# SNC8600.net
KiCad netlist of a schematic drawn in Altium Designer
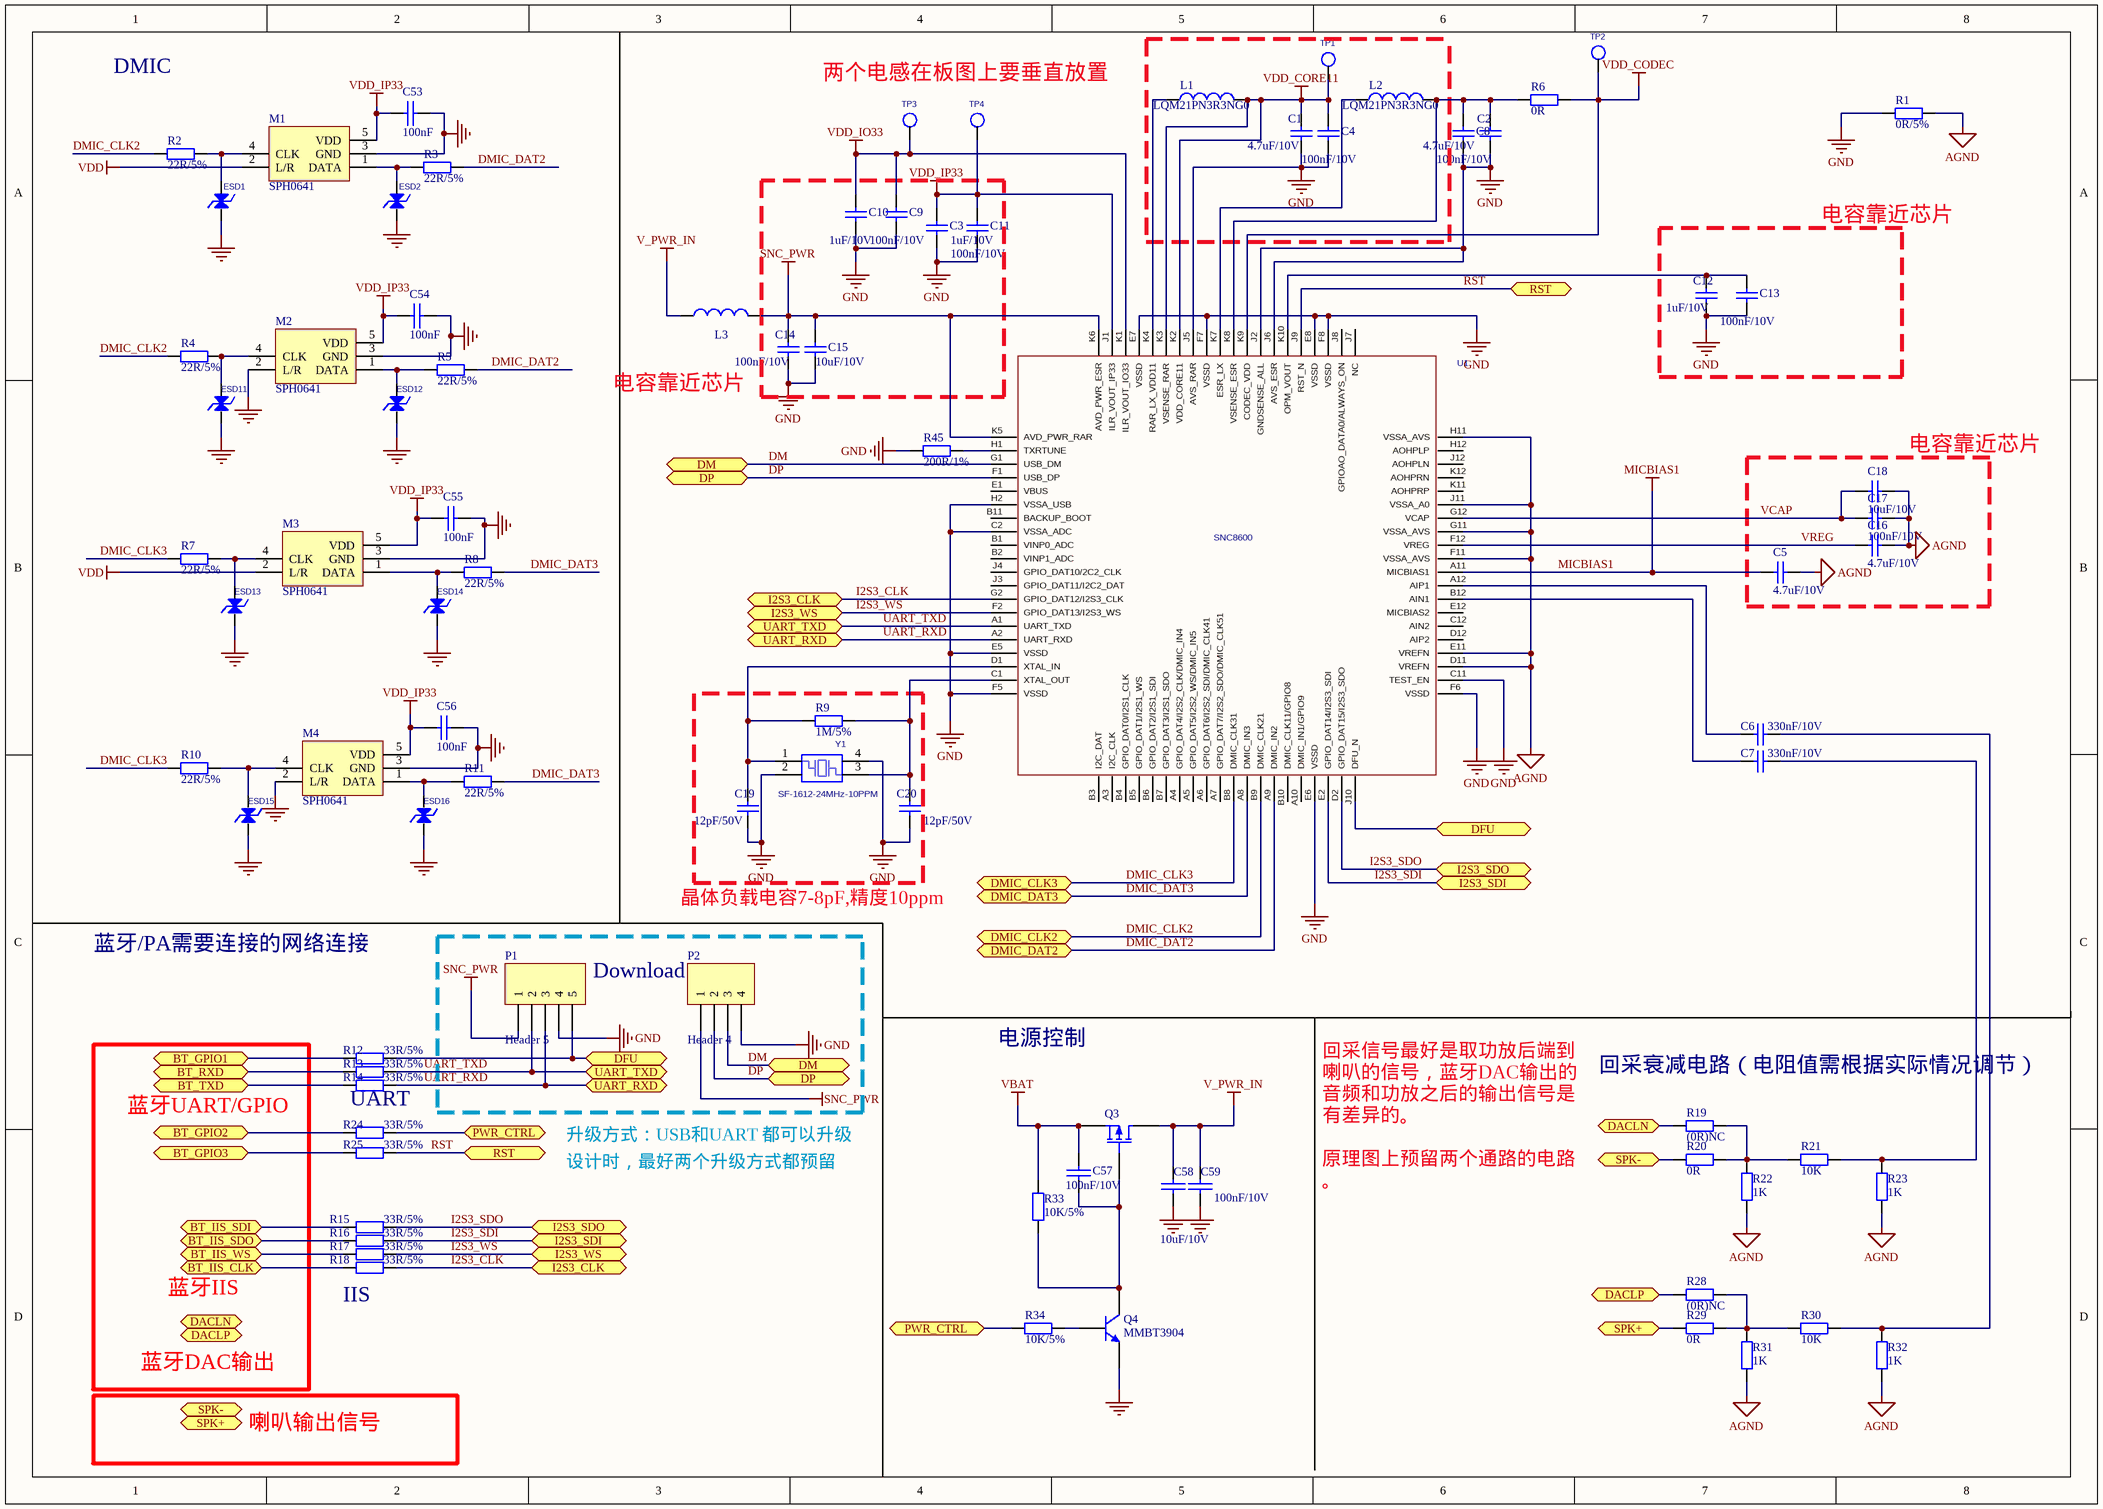
[diagram p0: SNC8600.SchDoc]

(export (version "E")
  (design (tool "Eeschema 10.0.6"))
  (components
    (comp (ref "C1")
      (value "4.7uF/10V")
      (footprint "C0603")
      (description "Capacitor (Semiconductor SIM Model)")
      (fields (field (name "PUBLISHER") "Altium Limited"))
      (libsource (lib "Miscellaneous Devices") (part "Cap Semi"))
    )
    (comp (ref "C2")
      (value "4.7uF/10V")
      (footprint "C0603")
      (description "Capacitor (Semiconductor SIM Model)")
      (fields (field (name "PUBLISHER") "Altium Limited"))
      (libsource (lib "Miscellaneous Devices") (part "Cap Semi"))
    )
    (comp (ref "C3")
      (value "1uF/10V")
      (footprint "C0603")
      (description "Capacitor (Semiconductor SIM Model)")
      (fields (field (name "PUBLISHER") "Altium Limited"))
      (libsource (lib "Miscellaneous Devices") (part "Cap Semi"))
    )
    (comp (ref "C4")
      (value "100nF/10V")
      (footprint "C0603")
      (description "Capacitor (Semiconductor SIM Model)")
      (fields (field (name "PUBLISHER") "Altium Limited"))
      (libsource (lib "Miscellaneous Devices") (part "Cap Semi"))
    )
    (comp (ref "C5")
      (value "4.7uF/10V")
      (footprint "C0603")
      (description "Capacitor (Semiconductor SIM Model)")
      (fields (field (name "PUBLISHER") "Altium Limited"))
      (libsource (lib "Miscellaneous Devices") (part "Cap Semi"))
    )
    (comp (ref "C6")
      (value "330nF/10V")
      (footprint "C0603")
      (description "Capacitor (Semiconductor SIM Model)")
      (fields (field (name "PUBLISHER") "Altium Limited"))
      (libsource (lib "Miscellaneous Devices") (part "Cap Semi"))
    )
    (comp (ref "C7")
      (value "330nF/10V")
      (footprint "C0603")
      (description "Capacitor (Semiconductor SIM Model)")
      (fields (field (name "PUBLISHER") "Altium Limited"))
      (libsource (lib "Miscellaneous Devices") (part "Cap Semi"))
    )
    (comp (ref "C8")
      (value "100nF/10V")
      (footprint "C0603")
      (description "Capacitor (Semiconductor SIM Model)")
      (fields (field (name "PUBLISHER") "Altium Limited"))
      (libsource (lib "Miscellaneous Devices") (part "Cap Semi"))
    )
    (comp (ref "C9")
      (value "100nF/10V")
      (footprint "C0603")
      (description "Capacitor (Semiconductor SIM Model)")
      (fields (field (name "PUBLISHER") "Altium Limited"))
      (libsource (lib "Miscellaneous Devices") (part "Cap Semi"))
    )
    (comp (ref "C10")
      (value "1uF/10V")
      (footprint "C0603")
      (description "Capacitor (Semiconductor SIM Model)")
      (fields (field (name "PUBLISHER") "Altium Limited"))
      (libsource (lib "Miscellaneous Devices") (part "Cap Semi"))
    )
    (comp (ref "C11")
      (value "100nF/10V")
      (footprint "C0603")
      (description "Capacitor (Semiconductor SIM Model)")
      (fields (field (name "PUBLISHER") "Altium Limited"))
      (libsource (lib "Miscellaneous Devices") (part "Cap Semi"))
    )
    (comp (ref "C12")
      (value "1uF/10V")
      (footprint "C0603")
      (description "Capacitor (Semiconductor SIM Model)")
      (fields (field (name "PUBLISHER") "Altium Limited"))
      (libsource (lib "Miscellaneous Devices") (part "Cap Semi"))
    )
    (comp (ref "C13")
      (value "100nF/10V")
      (footprint "C0603")
      (description "Capacitor (Semiconductor SIM Model)")
      (fields (field (name "PUBLISHER") "Altium Limited"))
      (libsource (lib "Miscellaneous Devices") (part "Cap Semi"))
    )
    (comp (ref "C14")
      (value "100nF/10V")
      (footprint "C0603")
      (description "Capacitor (Semiconductor SIM Model)")
      (fields (field (name "PUBLISHER") "Altium Limited"))
      (libsource (lib "Miscellaneous Devices") (part "Cap Semi"))
    )
    (comp (ref "C15")
      (value "10uF/10V")
      (footprint "C0603")
      (description "Capacitor (Semiconductor SIM Model)")
      (fields (field (name "PUBLISHER") "Altium Limited"))
      (libsource (lib "Miscellaneous Devices") (part "Cap Semi"))
    )
    (comp (ref "C16")
      (value "4.7uF/10V")
      (footprint "C0603")
      (description "Capacitor (Semiconductor SIM Model)")
      (fields (field (name "PUBLISHER") "Altium Limited"))
      (libsource (lib "Miscellaneous Devices") (part "Cap Semi"))
    )
    (comp (ref "C17")
      (value "100nF/10V")
      (footprint "C0603")
      (description "Capacitor (Semiconductor SIM Model)")
      (fields (field (name "PUBLISHER") "Altium Limited"))
      (libsource (lib "Miscellaneous Devices") (part "Cap Semi"))
    )
    (comp (ref "C18")
      (value "10uF/10V")
      (footprint "C0603")
      (description "Capacitor (Semiconductor SIM Model)")
      (fields (field (name "PUBLISHER") "Altium Limited"))
      (libsource (lib "Miscellaneous Devices") (part "Cap Semi"))
    )
    (comp (ref "C19")
      (value "12pF/50V")
      (footprint "C0603")
      (description "Capacitor (Semiconductor SIM Model)")
      (fields (field (name "PUBLISHER") "Altium Limited"))
      (libsource (lib "Miscellaneous Devices") (part "Cap Semi"))
    )
    (comp (ref "C20")
      (value "12pF/50V")
      (footprint "C0603")
      (description "Capacitor (Semiconductor SIM Model)")
      (fields (field (name "PUBLISHER") "Altium Limited"))
      (libsource (lib "Miscellaneous Devices") (part "Cap Semi"))
    )
    (comp (ref "C53")
      (value "100nF")
      (footprint "0201")
      (description "Capacitor")
      (libsource (lib "MIC1") (part "CAP-0201"))
    )
    (comp (ref "C54")
      (value "100nF")
      (footprint "0201")
      (description "Capacitor")
      (libsource (lib "MIC1") (part "CAP-0201"))
    )
    (comp (ref "C55")
      (value "100nF")
      (footprint "0201")
      (description "Capacitor")
      (libsource (lib "MIC1") (part "CAP-0201"))
    )
    (comp (ref "C56")
      (value "100nF")
      (footprint "0201")
      (description "Capacitor")
      (libsource (lib "MIC1") (part "CAP-0201"))
    )
    (comp (ref "C57")
      (value "100nF/10V")
      (footprint "0201")
      (description "Capacitor")
      (libsource (lib "*") (part "CAP"))
    )
    (comp (ref "C58")
      (value "10uF/10V")
      (footprint "C0402")
      (description "Capacitor")
      (libsource (lib "电容") (part "普通电容"))
    )
    (comp (ref "C59")
      (value "100nF/10V")
      (footprint "0201")
      (description "Capacitor")
      (libsource (lib "电容") (part "普通电容"))
    )
    (comp (ref "ESD1")
      (value "~")
      (footprint "0402 DFN")
      (libsource (lib "EVB-SCH-LCD-202003152") (part "ESD"))
    )
    (comp (ref "ESD2")
      (value "~")
      (footprint "0402 DFN")
      (libsource (lib "EVB-SCH-LCD-202003152") (part "ESD"))
    )
    (comp (ref "ESD11")
      (value "~")
      (footprint "0402 DFN")
      (libsource (lib "EVB-SCH-LCD-202003152") (part "ESD"))
    )
    (comp (ref "ESD12")
      (value "~")
      (footprint "0402 DFN")
      (libsource (lib "EVB-SCH-LCD-202003152") (part "ESD"))
    )
    (comp (ref "ESD13")
      (value "~")
      (footprint "0402 DFN")
      (libsource (lib "EVB-SCH-LCD-202003152") (part "ESD"))
    )
    (comp (ref "ESD14")
      (value "~")
      (footprint "0402 DFN")
      (libsource (lib "EVB-SCH-LCD-202003152") (part "ESD"))
    )
    (comp (ref "ESD15")
      (value "~")
      (footprint "0402 DFN")
      (libsource (lib "EVB-SCH-LCD-202003152") (part "ESD"))
    )
    (comp (ref "ESD16")
      (value "~")
      (footprint "0402 DFN")
      (libsource (lib "EVB-SCH-LCD-202003152") (part "ESD"))
    )
    (comp (ref "L1")
      (value "LQM21PN3R3NG0")
      (footprint "L0805")
      (description "Inductor")
      (fields (field (name "PUBLISHER") "Altium Limited"))
      (libsource (lib "Miscellaneous Devices") (part "Inductor"))
    )
    (comp (ref "L2")
      (value "LQM21PN3R3NG0")
      (footprint "L0805")
      (description "Inductor")
      (fields (field (name "PUBLISHER") "Altium Limited"))
      (libsource (lib "Miscellaneous Devices") (part "Inductor"))
    )
    (comp (ref "L3")
      (value "~")
      (footprint "R0402")
      (description "Inductor")
      (fields (field (name "PUBLISHER") "Altium Limited"))
      (libsource (lib "Miscellaneous Devices") (part "Inductor"))
    )
    (comp (ref "M1")
      (value "SPH0641")
      (footprint "SPH_3526")
      (description "MEMS MICPHONE")
      (fields (field (name "PUBLISHER") "Altium Limited"))
      (libsource (lib "MIC1") (part "SPH0641"))
    )
    (comp (ref "M2")
      (value "SPH0641")
      (footprint "SPH_3526")
      (description "MEMS MICPHONE")
      (fields (field (name "PUBLISHER") "Altium Limited"))
      (libsource (lib "MIC1") (part "SPH0641"))
    )
    (comp (ref "M3")
      (value "SPH0641")
      (footprint "SPH_3526")
      (description "MEMS MICPHONE")
      (fields (field (name "PUBLISHER") "Altium Limited"))
      (libsource (lib "MIC1") (part "SPH0641"))
    )
    (comp (ref "M4")
      (value "SPH0641")
      (footprint "SPH_3526")
      (description "MEMS MICPHONE")
      (fields (field (name "PUBLISHER") "Altium Limited"))
      (libsource (lib "MIC1") (part "SPH0641"))
    )
    (comp (ref "P1")
      (value "Header 5")
      (footprint "HDR1X5")
      (description "Header, 5-Pin")
      (fields (field (name "PUBLISHER") "Altium Limited"))
      (libsource (lib "Miscellaneous Connectors") (part "Header 5"))
    )
    (comp (ref "P2")
      (value "Header 4")
      (footprint "HDR1X4")
      (description "Header, 4-Pin")
      (fields (field (name "PUBLISHER") "Altium Limited"))
      (libsource (lib "Miscellaneous Connectors") (part "Header 4"))
    )
    (comp (ref "Q3")
      (value "~")
      (footprint "SOT23_3407")
      (description "P-Channel MOSFET")
      (fields (field (name "PUBLISHER") "Altium Limited"))
      (libsource (lib "Miscellaneous Devices") (part "MOSFET-P"))
    )
    (comp (ref "Q4")
      (value "MMBT3904")
      (footprint "SOT23")
      (description "NPN General Purpose Amplifier")
      (fields (field (name "PUBLISHER") "Altium Limited"))
      (libsource (lib "Miscellaneous Devices") (part "2N3904"))
    )
    (comp (ref "R1")
      (value "0R/5%")
      (footprint "R0603")
      (description "Resistor")
      (fields (field (name "PUBLISHER") "Altium Limited"))
      (libsource (lib "Miscellaneous Devices") (part "Res2"))
    )
    (comp (ref "R2")
      (value "22R/5%")
      (footprint "0201")
      (description "Resistor")
      (fields (field (name "PUBLISHER") "Altium Limited"))
      (libsource (lib "") (part "Res2_1"))
    )
    (comp (ref "R3")
      (value "22R/5%")
      (footprint "0201")
      (description "Resistor")
      (fields (field (name "PUBLISHER") "Altium Limited"))
      (libsource (lib "") (part "Res2_1"))
    )
    (comp (ref "R4")
      (value "22R/5%")
      (footprint "0201")
      (description "Resistor")
      (fields (field (name "PUBLISHER") "Altium Limited"))
      (libsource (lib "") (part "Res2_1"))
    )
    (comp (ref "R5")
      (value "22R/5%")
      (footprint "0201")
      (description "Resistor")
      (fields (field (name "PUBLISHER") "Altium Limited"))
      (libsource (lib "") (part "Res2_1"))
    )
    (comp (ref "R6")
      (value "0R")
      (footprint "R0603")
      (description "Resistor")
      (fields (field (name "PUBLISHER") "Altium Limited"))
      (libsource (lib "Miscellaneous Devices") (part "Res2"))
    )
    (comp (ref "R7")
      (value "22R/5%")
      (footprint "0201")
      (description "Resistor")
      (fields (field (name "PUBLISHER") "Altium Limited"))
      (libsource (lib "") (part "Res2_1"))
    )
    (comp (ref "R8")
      (value "22R/5%")
      (footprint "0201")
      (description "Resistor")
      (fields (field (name "PUBLISHER") "Altium Limited"))
      (libsource (lib "") (part "Res2_1"))
    )
    (comp (ref "R9")
      (value "1M/5%")
      (footprint "R0603")
      (description "Resistor")
      (fields (field (name "PUBLISHER") "Altium Limited"))
      (libsource (lib "Miscellaneous Devices") (part "Res2"))
    )
    (comp (ref "R10")
      (value "22R/5%")
      (footprint "0201")
      (description "Resistor")
      (fields (field (name "PUBLISHER") "Altium Limited"))
      (libsource (lib "") (part "Res2_1"))
    )
    (comp (ref "R11")
      (value "22R/5%")
      (footprint "0201")
      (description "Resistor")
      (fields (field (name "PUBLISHER") "Altium Limited"))
      (libsource (lib "") (part "Res2_1"))
    )
    (comp (ref "R12")
      (value "33R/5%")
      (footprint "R0603")
      (description "Resistor")
      (fields (field (name "PUBLISHER") "Altium Limited"))
      (libsource (lib "") (part "Res2_1"))
    )
    (comp (ref "R13")
      (value "33R/5%")
      (footprint "R0603")
      (description "Resistor")
      (fields (field (name "PUBLISHER") "Altium Limited"))
      (libsource (lib "") (part "Res2_1"))
    )
    (comp (ref "R14")
      (value "33R/5%")
      (footprint "R0603")
      (description "Resistor")
      (fields (field (name "PUBLISHER") "Altium Limited"))
      (libsource (lib "") (part "Res2_1"))
    )
    (comp (ref "R15")
      (value "33R/5%")
      (footprint "R0603")
      (description "Resistor")
      (fields (field (name "PUBLISHER") "Altium Limited"))
      (libsource (lib "") (part "Res2_1"))
    )
    (comp (ref "R16")
      (value "33R/5%")
      (footprint "R0603")
      (description "Resistor")
      (fields (field (name "PUBLISHER") "Altium Limited"))
      (libsource (lib "") (part "Res2_1"))
    )
    (comp (ref "R17")
      (value "33R/5%")
      (footprint "R0603")
      (description "Resistor")
      (fields (field (name "PUBLISHER") "Altium Limited"))
      (libsource (lib "") (part "Res2_1"))
    )
    (comp (ref "R18")
      (value "33R/5%")
      (footprint "R0603")
      (description "Resistor")
      (fields (field (name "PUBLISHER") "Altium Limited"))
      (libsource (lib "") (part "Res2_1"))
    )
    (comp (ref "R19")
      (value "(0R)NC")
      (footprint "R0603")
      (description "Resistor")
      (fields (field (name "PUBLISHER") "Altium Limited"))
      (libsource (lib "Miscellaneous Devices") (part "Res2"))
    )
    (comp (ref "R20")
      (value "0R")
      (footprint "R0603")
      (description "Resistor")
      (fields (field (name "PUBLISHER") "Altium Limited"))
      (libsource (lib "Miscellaneous Devices") (part "Res2"))
    )
    (comp (ref "R21")
      (value "10K")
      (footprint "R0603")
      (description "Resistor")
      (fields (field (name "PUBLISHER") "Altium Limited"))
      (libsource (lib "Miscellaneous Devices") (part "Res2"))
    )
    (comp (ref "R22")
      (value "1K")
      (footprint "R0603")
      (description "Resistor")
      (fields (field (name "PUBLISHER") "Altium Limited"))
      (libsource (lib "") (part "Res2_2"))
    )
    (comp (ref "R23")
      (value "1K")
      (footprint "R0603")
      (description "Resistor")
      (fields (field (name "PUBLISHER") "Altium Limited"))
      (libsource (lib "") (part "Res2_2"))
    )
    (comp (ref "R24")
      (value "33R/5%")
      (footprint "R0603")
      (description "Resistor")
      (fields (field (name "PUBLISHER") "Altium Limited"))
      (libsource (lib "") (part "Res2_1"))
    )
    (comp (ref "R25")
      (value "33R/5%")
      (footprint "R0603")
      (description "Resistor")
      (fields (field (name "PUBLISHER") "Altium Limited"))
      (libsource (lib "") (part "Res2_1"))
    )
    (comp (ref "R28")
      (value "(0R)NC")
      (footprint "R0603")
      (description "Resistor")
      (fields (field (name "PUBLISHER") "Altium Limited"))
      (libsource (lib "Miscellaneous Devices") (part "Res2"))
    )
    (comp (ref "R29")
      (value "0R")
      (footprint "R0603")
      (description "Resistor")
      (fields (field (name "PUBLISHER") "Altium Limited"))
      (libsource (lib "Miscellaneous Devices") (part "Res2"))
    )
    (comp (ref "R30")
      (value "10K")
      (footprint "R0603")
      (description "Resistor")
      (fields (field (name "PUBLISHER") "Altium Limited"))
      (libsource (lib "Miscellaneous Devices") (part "Res2"))
    )
    (comp (ref "R31")
      (value "1K")
      (footprint "R0603")
      (description "Resistor")
      (fields (field (name "PUBLISHER") "Altium Limited"))
      (libsource (lib "") (part "Res2_2"))
    )
    (comp (ref "R32")
      (value "1K")
      (footprint "R0603")
      (description "Resistor")
      (fields (field (name "PUBLISHER") "Altium Limited"))
      (libsource (lib "") (part "Res2_2"))
    )
    (comp (ref "R33")
      (value "10K/5%")
      (footprint "0201")
      (description "Resistor")
      (fields (field (name "PUBLISHER") "Altium Limited"))
      (libsource (lib "") (part "Res2_2"))
    )
    (comp (ref "R34")
      (value "10K/5%")
      (footprint "0201")
      (description "Resistor")
      (fields (field (name "PUBLISHER") "Altium Limited"))
      (libsource (lib "") (part "Res2_1"))
    )
    (comp (ref "R45")
      (value "200R/1%")
      (footprint "R0603")
      (description "Resistor")
      (fields (field (name "PUBLISHER") "Altium Limited"))
      (libsource (lib "") (part "Res2_1"))
    )
    (comp (ref "TP1")
      (value "TP1")
      (footprint "TP1-1MM")
      (libsource (lib "EVB-SCH-LCD-202003152") (part "TP1"))
    )
    (comp (ref "TP2")
      (value "TP1")
      (footprint "TP1-1MM")
      (libsource (lib "EVB-SCH-LCD-202003152") (part "TP1"))
    )
    (comp (ref "TP3")
      (value "TP1")
      (footprint "TP1-1MM")
      (libsource (lib "EVB-SCH-LCD-202003152") (part "TP1"))
    )
    (comp (ref "TP4")
      (value "TP1")
      (footprint "TP1-1MM")
      (libsource (lib "EVB-SCH-LCD-202003152") (part "TP1"))
    )
    (comp (ref "U1")
      (value "SNC8600")
      (footprint "BGA0405-2")
      (libsource (lib "EVB-SCH-LCD-202003152") (part "BGA_BCHIP-ES2"))
    )
    (comp (ref "Y1")
      (value "SF-1612-24MHz-10PPM")
      (footprint "SF1612")
      (fields (field (name "Comment") "SF1612"))
      (libsource (lib "EVB-SCH-LCD-202003152") (part "SF1612"))
    )
  )
  (nets
    (net (code "1") (name "/BT_GPIO1") (class "Default")
      (node (ref "R12") (pin "1") (pinfunction "1_1") (pintype "passive"))
    )
    (net (code "2") (name "/BT_GPIO2") (class "Default")
      (node (ref "R24") (pin "1") (pinfunction "1_1") (pintype "passive"))
    )
    (net (code "3") (name "/BT_GPIO3") (class "Default")
      (node (ref "R25") (pin "1") (pinfunction "1_1") (pintype "passive"))
    )
    (net (code "4") (name "/BT_IIS_CLK") (class "Default")
      (node (ref "R18") (pin "1") (pinfunction "1_1") (pintype "passive"))
    )
    (net (code "5") (name "/BT_IIS_SDI") (class "Default")
      (node (ref "R15") (pin "1") (pinfunction "1_1") (pintype "passive"))
    )
    (net (code "6") (name "/BT_IIS_SDO") (class "Default")
      (node (ref "R16") (pin "1") (pinfunction "1_1") (pintype "passive"))
    )
    (net (code "7") (name "/BT_IIS_WS") (class "Default")
      (node (ref "R17") (pin "1") (pinfunction "1_1") (pintype "passive"))
    )
    (net (code "8") (name "/BT_RXD") (class "Default")
      (node (ref "R13") (pin "1") (pinfunction "1_1") (pintype "passive"))
    )
    (net (code "9") (name "/BT_TXD") (class "Default")
      (node (ref "R14") (pin "1") (pinfunction "1_1") (pintype "passive"))
    )
    (net (code "10") (name "/DACLN") (class "Default")
      (node (ref "R19") (pin "2") (pinfunction "2_2") (pintype "passive"))
    )
    (net (code "11") (name "/DACLP") (class "Default")
      (node (ref "R28") (pin "2") (pinfunction "2_2") (pintype "passive"))
    )
    (net (code "12") (name "/DFU") (class "Default")
      (node (ref "P1") (pin "5") (pinfunction "5_5") (pintype "passive"))
      (node (ref "R12") (pin "2") (pinfunction "2_2") (pintype "passive"))
      (node (ref "U1") (pin "J10") (pinfunction "DFU_N_J10") (pintype "passive"))
    )
    (net (code "13") (name "/DM") (class "Default")
      (node (ref "P2") (pin "3") (pinfunction "3_3") (pintype "passive"))
      (node (ref "U1") (pin "G1") (pinfunction "USB_DM_G1") (pintype "passive"))
    )
    (net (code "14") (name "/DMIC_CLK2") (class "Default")
      (node (ref "R2") (pin "1") (pinfunction "1_1") (pintype "passive"))
      (node (ref "R4") (pin "1") (pinfunction "1_1") (pintype "passive"))
      (node (ref "U1") (pin "B9") (pinfunction "DMIC_CLK21_B9") (pintype "passive"))
    )
    (net (code "15") (name "/DMIC_CLK3") (class "Default")
      (node (ref "R10") (pin "1") (pinfunction "1_1") (pintype "passive"))
      (node (ref "R7") (pin "1") (pinfunction "1_1") (pintype "passive"))
      (node (ref "U1") (pin "B8") (pinfunction "DMIC_CLK31_B8") (pintype "passive"))
    )
    (net (code "16") (name "/DMIC_DAT2") (class "Default")
      (node (ref "R3") (pin "2") (pinfunction "2_2") (pintype "passive"))
      (node (ref "R5") (pin "2") (pinfunction "2_2") (pintype "passive"))
      (node (ref "U1") (pin "A9") (pinfunction "DMIC_IN2_A9") (pintype "passive"))
    )
    (net (code "17") (name "/DMIC_DAT3") (class "Default")
      (node (ref "R11") (pin "2") (pinfunction "2_2") (pintype "passive"))
      (node (ref "R8") (pin "2") (pinfunction "2_2") (pintype "passive"))
      (node (ref "U1") (pin "A8") (pinfunction "DMIC_IN3_A8") (pintype "passive"))
    )
    (net (code "18") (name "/DP") (class "Default")
      (node (ref "P2") (pin "2") (pinfunction "2_2") (pintype "passive"))
      (node (ref "U1") (pin "F1") (pinfunction "USB_DP_F1") (pintype "passive"))
    )
    (net (code "19") (name "/I2S3_CLK") (class "Default")
      (node (ref "R18") (pin "2") (pinfunction "2_2") (pintype "passive"))
      (node (ref "U1") (pin "G2") (pinfunction "GPIO_DAT12/I2S3_CLK_G2") (pintype "passive"))
    )
    (net (code "20") (name "/I2S3_SDI") (class "Default")
      (node (ref "R16") (pin "2") (pinfunction "2_2") (pintype "passive"))
      (node (ref "U1") (pin "E2") (pinfunction "GPIO_DAT14/I2S3_SDI_E2") (pintype "passive"))
    )
    (net (code "21") (name "/I2S3_SDO") (class "Default")
      (node (ref "R15") (pin "2") (pinfunction "2_2") (pintype "passive"))
      (node (ref "U1") (pin "D2") (pinfunction "GPIO_DAT15/I2S3_SDO_D2") (pintype "passive"))
    )
    (net (code "22") (name "/I2S3_WS") (class "Default")
      (node (ref "R17") (pin "2") (pinfunction "2_2") (pintype "passive"))
      (node (ref "U1") (pin "F2") (pinfunction "GPIO_DAT13/I2S3_WS_F2") (pintype "passive"))
    )
    (net (code "23") (name "/PWR_CTRL") (class "Default")
      (node (ref "R24") (pin "2") (pinfunction "2_2") (pintype "passive"))
      (node (ref "R34") (pin "1") (pinfunction "1_1") (pintype "passive"))
    )
    (net (code "24") (name "/RST") (class "Default")
      (node (ref "R25") (pin "2") (pinfunction "2_2") (pintype "passive"))
      (node (ref "U1") (pin "J9") (pinfunction "RST_N_J9") (pintype "passive"))
    )
    (net (code "25") (name "/SPK+") (class "Default")
      (node (ref "R29") (pin "2") (pinfunction "2_2") (pintype "passive"))
    )
    (net (code "26") (name "/SPK-") (class "Default")
      (node (ref "R20") (pin "2") (pinfunction "2_2") (pintype "passive"))
    )
    (net (code "27") (name "/UART_RXD") (class "Default")
      (node (ref "P1") (pin "3") (pinfunction "3_3") (pintype "passive"))
      (node (ref "R14") (pin "2") (pinfunction "2_2") (pintype "passive"))
      (node (ref "U1") (pin "A2") (pinfunction "UART_RXD_A2") (pintype "passive"))
    )
    (net (code "28") (name "/UART_TXD") (class "Default")
      (node (ref "P1") (pin "2") (pinfunction "2_2") (pintype "passive"))
      (node (ref "R13") (pin "2") (pinfunction "2_2") (pintype "passive"))
      (node (ref "U1") (pin "A1") (pinfunction "UART_TXD_A1") (pintype "passive"))
    )
    (net (code "29") (name "/VCAP") (class "Default")
      (node (ref "C17") (pin "2") (pinfunction "2_2") (pintype "passive"))
      (node (ref "C18") (pin "2") (pinfunction "2_2") (pintype "passive"))
      (node (ref "U1") (pin "G12") (pinfunction "VCAP_G12") (pintype "passive"))
    )
    (net (code "30") (name "/VREG") (class "Default")
      (node (ref "C16") (pin "2") (pinfunction "2_2") (pintype "passive"))
      (node (ref "U1") (pin "F12") (pinfunction "VREG_F12") (pintype "passive"))
    )
    (net (code "31") (name "AGND") (class "Default")
      (node (ref "C16") (pin "1") (pinfunction "1_1") (pintype "passive"))
      (node (ref "C17") (pin "1") (pinfunction "1_1") (pintype "passive"))
      (node (ref "C18") (pin "1") (pinfunction "1_1") (pintype "passive"))
      (node (ref "C5") (pin "1") (pinfunction "1_1") (pintype "passive"))
      (node (ref "R1") (pin "1") (pinfunction "1_1") (pintype "passive"))
      (node (ref "R22") (pin "2") (pinfunction "2_2") (pintype "passive"))
      (node (ref "R23") (pin "2") (pinfunction "2_2") (pintype "passive"))
      (node (ref "R31") (pin "2") (pinfunction "2_2") (pintype "passive"))
      (node (ref "R32") (pin "2") (pinfunction "2_2") (pintype "passive"))
      (node (ref "U1") (pin "D11") (pinfunction "VREFN_D11") (pintype "passive"))
      (node (ref "U1") (pin "E11") (pinfunction "VREFN_E11") (pintype "passive"))
      (node (ref "U1") (pin "F11") (pinfunction "VSSA_AVS_F11") (pintype "passive"))
      (node (ref "U1") (pin "G11") (pinfunction "VSSA_AVS_G11") (pintype "passive"))
      (node (ref "U1") (pin "H11") (pinfunction "VSSA_AVS_H11") (pintype "passive"))
      (node (ref "U1") (pin "J11") (pinfunction "VSSA_A0_J11") (pintype "passive"))
    )
    (net (code "32") (name "GND") (class "Default")
      (node (ref "C1") (pin "1") (pinfunction "1_1") (pintype "passive"))
      (node (ref "C10") (pin "1") (pinfunction "1_1") (pintype "passive"))
      (node (ref "C11") (pin "1") (pinfunction "1_1") (pintype "passive"))
      (node (ref "C12") (pin "1") (pinfunction "1_1") (pintype "passive"))
      (node (ref "C13") (pin "1") (pinfunction "1_1") (pintype "passive"))
      (node (ref "C14") (pin "1") (pinfunction "1_1") (pintype "passive"))
      (node (ref "C15") (pin "1") (pinfunction "1_1") (pintype "passive"))
      (node (ref "C19") (pin "1") (pinfunction "1_1") (pintype "passive"))
      (node (ref "C2") (pin "1") (pinfunction "1_1") (pintype "passive"))
      (node (ref "C20") (pin "1") (pinfunction "1_1") (pintype "passive"))
      (node (ref "C3") (pin "1") (pinfunction "1_1") (pintype "passive"))
      (node (ref "C4") (pin "1") (pinfunction "1_1") (pintype "passive"))
      (node (ref "C53") (pin "1") (pinfunction "1_1") (pintype "passive"))
      (node (ref "C54") (pin "1") (pinfunction "1_1") (pintype "passive"))
      (node (ref "C55") (pin "1") (pinfunction "1_1") (pintype "passive"))
      (node (ref "C56") (pin "1") (pinfunction "1_1") (pintype "passive"))
      (node (ref "C58") (pin "1") (pinfunction "1_1") (pintype "passive"))
      (node (ref "C59") (pin "1") (pinfunction "1_1") (pintype "passive"))
      (node (ref "C8") (pin "1") (pinfunction "1_1") (pintype "passive"))
      (node (ref "C9") (pin "1") (pinfunction "1_1") (pintype "passive"))
      (node (ref "ESD1") (pin "2") (pinfunction "2_2") (pintype "passive"))
      (node (ref "ESD11") (pin "2") (pinfunction "2_2") (pintype "passive"))
      (node (ref "ESD12") (pin "2") (pinfunction "2_2") (pintype "passive"))
      (node (ref "ESD13") (pin "2") (pinfunction "2_2") (pintype "passive"))
      (node (ref "ESD14") (pin "2") (pinfunction "2_2") (pintype "passive"))
      (node (ref "ESD15") (pin "2") (pinfunction "2_2") (pintype "passive"))
      (node (ref "ESD16") (pin "2") (pinfunction "2_2") (pintype "passive"))
      (node (ref "ESD2") (pin "2") (pinfunction "2_2") (pintype "passive"))
      (node (ref "M1") (pin "3") (pinfunction "GND_3") (pintype "power_in"))
      (node (ref "M2") (pin "2") (pinfunction "L/R_2") (pintype "passive"))
      (node (ref "M2") (pin "3") (pinfunction "GND_3") (pintype "power_in"))
      (node (ref "M3") (pin "3") (pinfunction "GND_3") (pintype "power_in"))
      (node (ref "M4") (pin "2") (pinfunction "L/R_2") (pintype "passive"))
      (node (ref "M4") (pin "3") (pinfunction "GND_3") (pintype "power_in"))
      (node (ref "P1") (pin "4") (pinfunction "4_4") (pintype "passive"))
      (node (ref "P2") (pin "4") (pinfunction "4_4") (pintype "passive"))
      (node (ref "Q4") (pin "2") (pinfunction "E_2") (pintype "passive"))
      (node (ref "R1") (pin "2") (pinfunction "2_2") (pintype "passive"))
      (node (ref "R45") (pin "1") (pinfunction "1_1") (pintype "passive"))
      (node (ref "U1") (pin "C11") (pinfunction "TEST_EN_C11") (pintype "passive"))
      (node (ref "U1") (pin "C2") (pinfunction "VSSA_ADC_C2") (pintype "passive"))
      (node (ref "U1") (pin "E5") (pinfunction "VSSD_E5") (pintype "passive"))
      (node (ref "U1") (pin "E6") (pinfunction "VSSD_E6") (pintype "passive"))
      (node (ref "U1") (pin "E7") (pinfunction "VSSD_E7") (pintype "passive"))
      (node (ref "U1") (pin "E8") (pinfunction "VSSD_E8") (pintype "passive"))
      (node (ref "U1") (pin "F5") (pinfunction "VSSD_F5") (pintype "passive"))
      (node (ref "U1") (pin "F6") (pinfunction "VSSD_F6") (pintype "passive"))
      (node (ref "U1") (pin "F7") (pinfunction "VSSD_F7") (pintype "passive"))
      (node (ref "U1") (pin "F8") (pinfunction "VSSD_F8") (pintype "passive"))
      (node (ref "U1") (pin "H2") (pinfunction "VSSA_USB_H2") (pintype "passive"))
      (node (ref "U1") (pin "J2") (pinfunction "GNDSENSE_ALL_J2") (pintype "passive"))
      (node (ref "U1") (pin "J5") (pinfunction "AVS_RAR_J5") (pintype "passive"))
      (node (ref "U1") (pin "J6") (pinfunction "AVS_ESR_J6") (pintype "passive"))
      (node (ref "Y1") (pin "2") (pinfunction "2_2") (pintype "passive"))
      (node (ref "Y1") (pin "4") (pinfunction "4_4") (pintype "passive"))
    )
    (net (code "33") (name "MICBIAS1") (class "Default")
      (node (ref "C5") (pin "2") (pinfunction "2_2") (pintype "passive"))
      (node (ref "U1") (pin "A11") (pinfunction "MICBIAS1_A11") (pintype "passive"))
    )
    (net (code "34") (name "Net-(C6-Pad1)") (class "Default")
      (node (ref "C6") (pin "1") (pinfunction "1_1") (pintype "passive"))
      (node (ref "R30") (pin "1") (pinfunction "1_1") (pintype "passive"))
      (node (ref "R32") (pin "1") (pinfunction "1_1") (pintype "passive"))
    )
    (net (code "35") (name "Net-(C7-Pad1)") (class "Default")
      (node (ref "C7") (pin "1") (pinfunction "1_1") (pintype "passive"))
      (node (ref "R21") (pin "1") (pinfunction "1_1") (pintype "passive"))
      (node (ref "R23") (pin "1") (pinfunction "1_1") (pintype "passive"))
    )
    (net (code "36") (name "Net-(M1-CLK)") (class "Default")
      (node (ref "ESD1") (pin "1") (pinfunction "1_1") (pintype "passive"))
      (node (ref "M1") (pin "4") (pinfunction "CLK_4") (pintype "power_in"))
      (node (ref "R2") (pin "2") (pinfunction "2_2") (pintype "passive"))
    )
    (net (code "37") (name "Net-(M1-DATA)") (class "Default")
      (node (ref "ESD2") (pin "1") (pinfunction "1_1") (pintype "passive"))
      (node (ref "M1") (pin "1") (pinfunction "DATA_1") (pintype "passive"))
      (node (ref "R3") (pin "1") (pinfunction "1_1") (pintype "passive"))
    )
    (net (code "38") (name "Net-(M2-CLK)") (class "Default")
      (node (ref "ESD11") (pin "1") (pinfunction "1_1") (pintype "passive"))
      (node (ref "M2") (pin "4") (pinfunction "CLK_4") (pintype "power_in"))
      (node (ref "R4") (pin "2") (pinfunction "2_2") (pintype "passive"))
    )
    (net (code "39") (name "Net-(M2-DATA)") (class "Default")
      (node (ref "ESD12") (pin "1") (pinfunction "1_1") (pintype "passive"))
      (node (ref "M2") (pin "1") (pinfunction "DATA_1") (pintype "passive"))
      (node (ref "R5") (pin "1") (pinfunction "1_1") (pintype "passive"))
    )
    (net (code "40") (name "Net-(M3-CLK)") (class "Default")
      (node (ref "ESD13") (pin "1") (pinfunction "1_1") (pintype "passive"))
      (node (ref "M3") (pin "4") (pinfunction "CLK_4") (pintype "power_in"))
      (node (ref "R7") (pin "2") (pinfunction "2_2") (pintype "passive"))
    )
    (net (code "41") (name "Net-(M3-DATA)") (class "Default")
      (node (ref "ESD14") (pin "1") (pinfunction "1_1") (pintype "passive"))
      (node (ref "M3") (pin "1") (pinfunction "DATA_1") (pintype "passive"))
      (node (ref "R8") (pin "1") (pinfunction "1_1") (pintype "passive"))
    )
    (net (code "42") (name "Net-(M4-CLK)") (class "Default")
      (node (ref "ESD15") (pin "1") (pinfunction "1_1") (pintype "passive"))
      (node (ref "M4") (pin "4") (pinfunction "CLK_4") (pintype "power_in"))
      (node (ref "R10") (pin "2") (pinfunction "2_2") (pintype "passive"))
    )
    (net (code "43") (name "Net-(M4-DATA)") (class "Default")
      (node (ref "ESD16") (pin "1") (pinfunction "1_1") (pintype "passive"))
      (node (ref "M4") (pin "1") (pinfunction "DATA_1") (pintype "passive"))
      (node (ref "R11") (pin "1") (pinfunction "1_1") (pintype "passive"))
    )
    (net (code "44") (name "Net-(Q3-G)") (class "Default")
      (node (ref "C57") (pin "1") (pinfunction "1_1") (pintype "passive"))
      (node (ref "Q3") (pin "2") (pinfunction "G_2") (pintype "passive"))
      (node (ref "Q4") (pin "3") (pinfunction "C_3") (pintype "passive"))
      (node (ref "R33") (pin "2") (pinfunction "2_2") (pintype "passive"))
    )
    (net (code "45") (name "Net-(Q4-B)") (class "Default")
      (node (ref "Q4") (pin "1") (pinfunction "B_1") (pintype "passive"))
      (node (ref "R34") (pin "2") (pinfunction "2_2") (pintype "passive"))
    )
    (net (code "46") (name "Net-(R19-Pad1)") (class "Default")
      (node (ref "R19") (pin "1") (pinfunction "1_1") (pintype "passive"))
      (node (ref "R20") (pin "1") (pinfunction "1_1") (pintype "passive"))
      (node (ref "R21") (pin "2") (pinfunction "2_2") (pintype "passive"))
      (node (ref "R22") (pin "1") (pinfunction "1_1") (pintype "passive"))
    )
    (net (code "47") (name "Net-(R28-Pad1)") (class "Default")
      (node (ref "R28") (pin "1") (pinfunction "1_1") (pintype "passive"))
      (node (ref "R29") (pin "1") (pinfunction "1_1") (pintype "passive"))
      (node (ref "R30") (pin "2") (pinfunction "2_2") (pintype "passive"))
      (node (ref "R31") (pin "1") (pinfunction "1_1") (pintype "passive"))
    )
    (net (code "48") (name "Net-(U1-AIN1)") (class "Default")
      (node (ref "C7") (pin "2") (pinfunction "2_2") (pintype "passive"))
      (node (ref "U1") (pin "B12") (pinfunction "AIN1_B12") (pintype "passive"))
    )
    (net (code "49") (name "Net-(U1-AIP1)") (class "Default")
      (node (ref "C6") (pin "2") (pinfunction "2_2") (pintype "passive"))
      (node (ref "U1") (pin "A12") (pinfunction "AIP1_A12") (pintype "passive"))
    )
    (net (code "50") (name "Net-(U1-ESR_LX)") (class "Default")
      (node (ref "L2") (pin "1") (pinfunction "1_1") (pintype "passive"))
      (node (ref "U1") (pin "K7") (pinfunction "ESR_LX_K7") (pintype "passive"))
    )
    (net (code "51") (name "Net-(U1-OPM_VOUT)") (class "Default")
      (node (ref "C12") (pin "2") (pinfunction "2_2") (pintype "passive"))
      (node (ref "C13") (pin "2") (pinfunction "2_2") (pintype "passive"))
      (node (ref "U1") (pin "K10") (pinfunction "OPM_VOUT_K10") (pintype "passive"))
    )
    (net (code "52") (name "Net-(U1-RAR_LX_VDD11)") (class "Default")
      (node (ref "L1") (pin "1") (pinfunction "1_1") (pintype "passive"))
      (node (ref "U1") (pin "K4") (pinfunction "RAR_LX_VDD11_K4") (pintype "passive"))
    )
    (net (code "53") (name "Net-(U1-TXRTUNE)") (class "Default")
      (node (ref "R45") (pin "2") (pinfunction "2_2") (pintype "passive"))
      (node (ref "U1") (pin "H1") (pinfunction "TXRTUNE_H1") (pintype "passive"))
    )
    (net (code "54") (name "Net-(U1-VSENSE_ESR)") (class "Default")
      (node (ref "C2") (pin "2") (pinfunction "2_2") (pintype "passive"))
      (node (ref "C8") (pin "2") (pinfunction "2_2") (pintype "passive"))
      (node (ref "L2") (pin "2") (pinfunction "2_2") (pintype "passive"))
      (node (ref "R6") (pin "2") (pinfunction "2_2") (pintype "passive"))
      (node (ref "U1") (pin "K8") (pinfunction "VSENSE_ESR_K8") (pintype "passive"))
    )
    (net (code "55") (name "Net-(U1-XTAL_IN)") (class "Default")
      (node (ref "C19") (pin "2") (pinfunction "2_2") (pintype "passive"))
      (node (ref "R9") (pin "2") (pinfunction "2_2") (pintype "passive"))
      (node (ref "U1") (pin "D1") (pinfunction "XTAL_IN_D1") (pintype "passive"))
      (node (ref "Y1") (pin "1") (pinfunction "1_1") (pintype "passive"))
    )
    (net (code "56") (name "Net-(U1-XTAL_OUT)") (class "Default")
      (node (ref "C20") (pin "2") (pinfunction "2_2") (pintype "passive"))
      (node (ref "R9") (pin "1") (pinfunction "1_1") (pintype "passive"))
      (node (ref "U1") (pin "C1") (pinfunction "XTAL_OUT_C1") (pintype "passive"))
      (node (ref "Y1") (pin "3") (pinfunction "3_3") (pintype "passive"))
    )
    (net (code "57") (name "SNC_PWR") (class "Default")
      (node (ref "C14") (pin "2") (pinfunction "2_2") (pintype "passive"))
      (node (ref "C15") (pin "2") (pinfunction "2_2") (pintype "passive"))
      (node (ref "L3") (pin "2") (pinfunction "2_2") (pintype "passive"))
      (node (ref "P1") (pin "1") (pinfunction "1_1") (pintype "passive"))
      (node (ref "P2") (pin "1") (pinfunction "1_1") (pintype "passive"))
      (node (ref "U1") (pin "K5") (pinfunction "AVD_PWR_RAR_K5") (pintype "passive"))
      (node (ref "U1") (pin "K6") (pinfunction "AVD_PWR_ESR_K6") (pintype "passive"))
    )
    (net (code "58") (name "VBAT") (class "Default")
      (node (ref "C57") (pin "2") (pinfunction "2_2") (pintype "passive"))
      (node (ref "Q3") (pin "3") (pinfunction "S_3") (pintype "passive"))
      (node (ref "R33") (pin "1") (pinfunction "1_1") (pintype "passive"))
    )
    (net (code "59") (name "VDD") (class "Default")
      (node (ref "M1") (pin "2") (pinfunction "L/R_2") (pintype "passive"))
      (node (ref "M3") (pin "2") (pinfunction "L/R_2") (pintype "passive"))
    )
    (net (code "60") (name "VDD_CODEC") (class "Default")
      (node (ref "R6") (pin "1") (pinfunction "1_1") (pintype "passive"))
      (node (ref "TP2") (pin "1") (pinfunction "1_1") (pintype "passive"))
      (node (ref "U1") (pin "K9") (pinfunction "CODEC_VDD_K9") (pintype "passive"))
    )
    (net (code "61") (name "VDD_CORE11") (class "Default")
      (node (ref "C1") (pin "2") (pinfunction "2_2") (pintype "passive"))
      (node (ref "C4") (pin "2") (pinfunction "2_2") (pintype "passive"))
      (node (ref "L1") (pin "2") (pinfunction "2_2") (pintype "passive"))
      (node (ref "TP1") (pin "1") (pinfunction "1_1") (pintype "passive"))
      (node (ref "U1") (pin "K2") (pinfunction "VDD_CORE11_K2") (pintype "passive"))
      (node (ref "U1") (pin "K3") (pinfunction "VSENSE_RAR_K3") (pintype "passive"))
    )
    (net (code "62") (name "VDD_IO33") (class "Default")
      (node (ref "C10") (pin "2") (pinfunction "2_2") (pintype "passive"))
      (node (ref "C9") (pin "2") (pinfunction "2_2") (pintype "passive"))
      (node (ref "TP3") (pin "1") (pinfunction "1_1") (pintype "passive"))
      (node (ref "U1") (pin "K1") (pinfunction "ILR_VOUT_IO33_K1") (pintype "passive"))
    )
    (net (code "63") (name "VDD_IP33") (class "Default")
      (node (ref "C11") (pin "2") (pinfunction "2_2") (pintype "passive"))
      (node (ref "C3") (pin "2") (pinfunction "2_2") (pintype "passive"))
      (node (ref "C53") (pin "2") (pinfunction "2_2") (pintype "passive"))
      (node (ref "C54") (pin "2") (pinfunction "2_2") (pintype "passive"))
      (node (ref "C55") (pin "2") (pinfunction "2_2") (pintype "passive"))
      (node (ref "C56") (pin "2") (pinfunction "2_2") (pintype "passive"))
      (node (ref "M1") (pin "5") (pinfunction "VDD_5") (pintype "power_in"))
      (node (ref "M2") (pin "5") (pinfunction "VDD_5") (pintype "power_in"))
      (node (ref "M3") (pin "5") (pinfunction "VDD_5") (pintype "power_in"))
      (node (ref "M4") (pin "5") (pinfunction "VDD_5") (pintype "power_in"))
      (node (ref "TP4") (pin "1") (pinfunction "1_1") (pintype "passive"))
      (node (ref "U1") (pin "J1") (pinfunction "ILR_VOUT_IP33_J1") (pintype "passive"))
    )
    (net (code "64") (name "V_PWR_IN") (class "Default")
      (node (ref "C58") (pin "2") (pinfunction "2_2") (pintype "passive"))
      (node (ref "C59") (pin "2") (pinfunction "2_2") (pintype "passive"))
      (node (ref "L3") (pin "1") (pinfunction "1_1") (pintype "passive"))
      (node (ref "Q3") (pin "1") (pinfunction "D_1") (pintype "passive"))
    )
    (net (code "65") (name "unconnected-(U1-AIN2-PadC12)") (class "Default")
      (node (ref "U1") (pin "C12") (pinfunction "AIN2_C12") (pintype "passive"))
    )
    (net (code "66") (name "unconnected-(U1-AIP2-PadD12)") (class "Default")
      (node (ref "U1") (pin "D12") (pinfunction "AIP2_D12") (pintype "passive"))
    )
    (net (code "67") (name "unconnected-(U1-AOHPLN-PadJ12)") (class "Default")
      (node (ref "U1") (pin "J12") (pinfunction "AOHPLN_J12") (pintype "passive"))
    )
    (net (code "68") (name "unconnected-(U1-AOHPLP-PadH12)") (class "Default")
      (node (ref "U1") (pin "H12") (pinfunction "AOHPLP_H12") (pintype "passive"))
    )
    (net (code "69") (name "unconnected-(U1-AOHPRN-PadK12)") (class "Default")
      (node (ref "U1") (pin "K12") (pinfunction "AOHPRN_K12") (pintype "passive"))
    )
    (net (code "70") (name "unconnected-(U1-AOHPRP-PadK11)") (class "Default")
      (node (ref "U1") (pin "K11") (pinfunction "AOHPRP_K11") (pintype "passive"))
    )
    (net (code "71") (name "unconnected-(U1-BACKUP_BOOT-PadB11)") (class "Default")
      (node (ref "U1") (pin "B11") (pinfunction "BACKUP_BOOT_B11") (pintype "passive"))
    )
    (net (code "72") (name "unconnected-(U1-DMIC_CLK11{slash}GPIO8-PadB10)") (class "Default")
      (node (ref "U1") (pin "B10") (pinfunction "DMIC_CLK11/GPIO8_B10") (pintype "passive"))
    )
    (net (code "73") (name "unconnected-(U1-DMIC_IN1{slash}GPIO9-PadA10)") (class "Default")
      (node (ref "U1") (pin "A10") (pinfunction "DMIC_IN1/GPIO9_A10") (pintype "passive"))
    )
    (net (code "74") (name "unconnected-(U1-GPIOAO_DATA0{slash}ALWAYS_ON-PadJ8)") (class "Default")
      (node (ref "U1") (pin "J8") (pinfunction "GPIOAO_DATA0/ALWAYS_ON_J8") (pintype "passive"))
    )
    (net (code "75") (name "unconnected-(U1-GPIO_DAT0{slash}I2S1_CLK-PadB4)") (class "Default")
      (node (ref "U1") (pin "B4") (pinfunction "GPIO_DAT0/I2S1_CLK_B4") (pintype "passive"))
    )
    (net (code "76") (name "unconnected-(U1-GPIO_DAT1{slash}I2S1_WS-PadB5)") (class "Default")
      (node (ref "U1") (pin "B5") (pinfunction "GPIO_DAT1/I2S1_WS_B5") (pintype "passive"))
    )
    (net (code "77") (name "unconnected-(U1-GPIO_DAT2{slash}I2S1_SDI-PadB6)") (class "Default")
      (node (ref "U1") (pin "B6") (pinfunction "GPIO_DAT2/I2S1_SDI_B6") (pintype "passive"))
    )
    (net (code "78") (name "unconnected-(U1-GPIO_DAT3{slash}I2S1_SDO-PadB7)") (class "Default")
      (node (ref "U1") (pin "B7") (pinfunction "GPIO_DAT3/I2S1_SDO_B7") (pintype "passive"))
    )
    (net (code "79") (name "unconnected-(U1-GPIO_DAT4{slash}I2S2_CLK{slash}DMIC_IN4-PadA4)") (class "Default")
      (node (ref "U1") (pin "A4") (pinfunction "GPIO_DAT4/I2S2_CLK/DMIC_IN4_A4") (pintype "passive"))
    )
    (net (code "80") (name "unconnected-(U1-GPIO_DAT5{slash}I2S2_WS{slash}DMIC_IN5-PadA5)") (class "Default")
      (node (ref "U1") (pin "A5") (pinfunction "GPIO_DAT5/I2S2_WS/DMIC_IN5_A5") (pintype "passive"))
    )
    (net (code "81") (name "unconnected-(U1-GPIO_DAT6{slash}I2S2_SDI{slash}DMIC_CLK41-PadA6)") (class "Default")
      (node (ref "U1") (pin "A6") (pinfunction "GPIO_DAT6/I2S2_SDI/DMIC_CLK41_A6") (pintype "passive"))
    )
    (net (code "82") (name "unconnected-(U1-GPIO_DAT7{slash}I2S2_SDO{slash}DMIC_CLK51-PadA7)") (class "Default")
      (node (ref "U1") (pin "A7") (pinfunction "GPIO_DAT7/I2S2_SDO/DMIC_CLK51_A7") (pintype "passive"))
    )
    (net (code "83") (name "unconnected-(U1-GPIO_DAT10{slash}2C2_CLK-PadJ4)") (class "Default")
      (node (ref "U1") (pin "J4") (pinfunction "GPIO_DAT10/2C2_CLK_J4") (pintype "passive"))
    )
    (net (code "84") (name "unconnected-(U1-GPIO_DAT11{slash}I2C2_DAT-PadJ3)") (class "Default")
      (node (ref "U1") (pin "J3") (pinfunction "GPIO_DAT11/I2C2_DAT_J3") (pintype "passive"))
    )
    (net (code "85") (name "unconnected-(U1-I2C_CLK-PadA3)") (class "Default")
      (node (ref "U1") (pin "A3") (pinfunction "I2C_CLK_A3") (pintype "passive"))
    )
    (net (code "86") (name "unconnected-(U1-I2C_DAT-PadB3)") (class "Default")
      (node (ref "U1") (pin "B3") (pinfunction "I2C_DAT_B3") (pintype "passive"))
    )
    (net (code "87") (name "unconnected-(U1-MICBIAS2-PadE12)") (class "Default")
      (node (ref "U1") (pin "E12") (pinfunction "MICBIAS2_E12") (pintype "passive"))
    )
    (net (code "88") (name "unconnected-(U1-NC-PadJ7)") (class "Default")
      (node (ref "U1") (pin "J7") (pinfunction "NC_J7") (pintype "passive"))
    )
    (net (code "89") (name "unconnected-(U1-VBUS-PadE1)") (class "Default")
      (node (ref "U1") (pin "E1") (pinfunction "VBUS_E1") (pintype "passive"))
    )
    (net (code "90") (name "unconnected-(U1-VINP0_ADC-PadB1)") (class "Default")
      (node (ref "U1") (pin "B1") (pinfunction "VINP0_ADC_B1") (pintype "passive"))
    )
    (net (code "91") (name "unconnected-(U1-VINP1_ADC-PadB2)") (class "Default")
      (node (ref "U1") (pin "B2") (pinfunction "VINP1_ADC_B2") (pintype "passive"))
    )
  )
)
